# EasyedaPrj_POCKET_DICE_2026-03-14.net
KiCad netlist of a schematic drawn in EasyEDA Pro
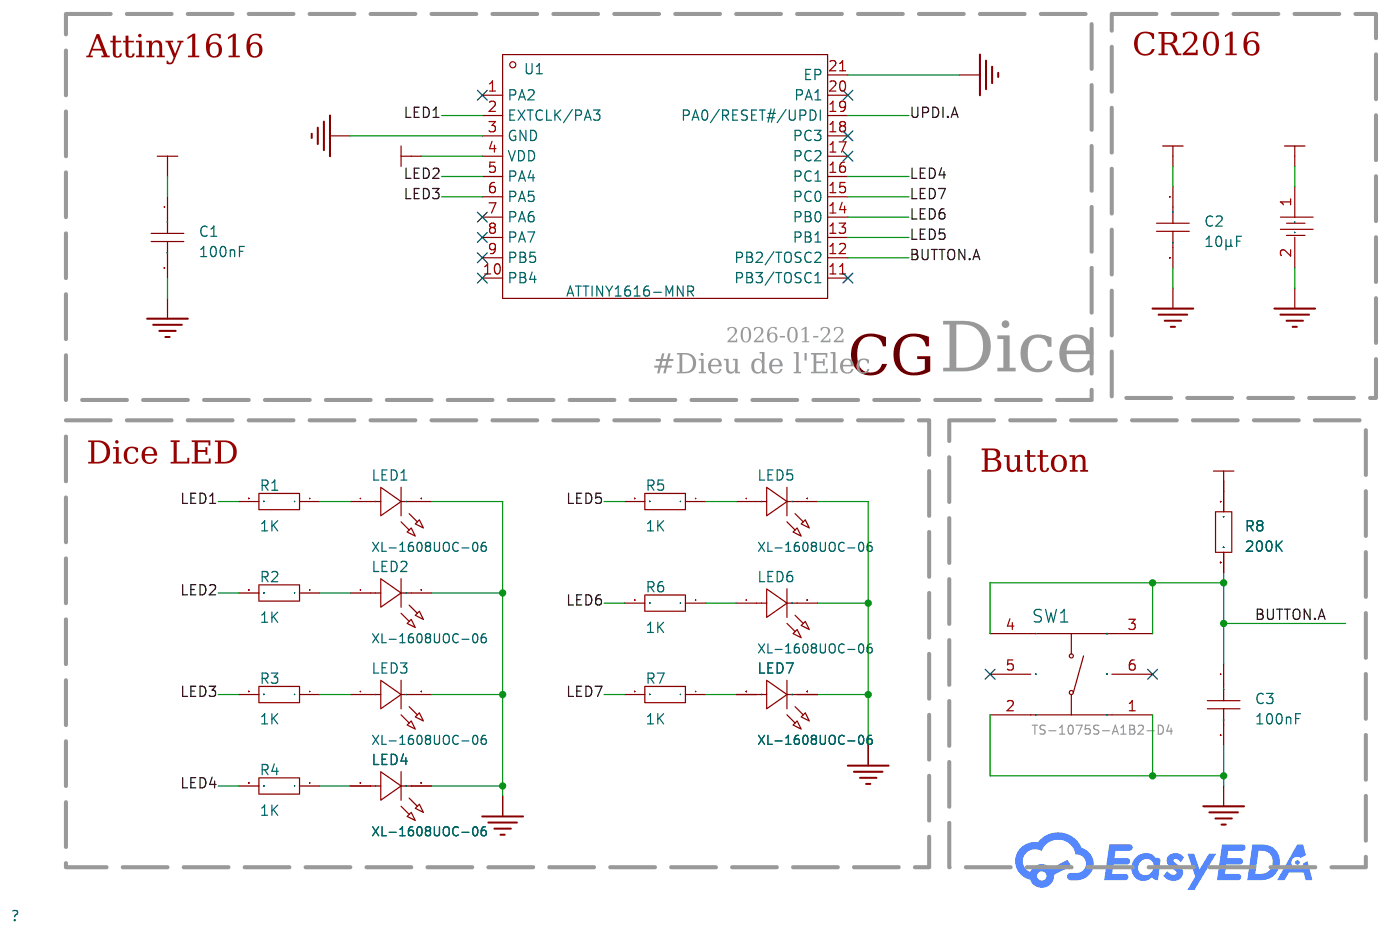
[diagram p0: schematic sheet]

(export (version "E")
  (design (tool "Eeschema 10.0.6"))
  (components
    (comp (ref "C1")
      (value "100nF")
      (footprint "easyedapro:C0805")
      (libsource (lib "easyedapro") (part "CAP"))
    )
    (comp (ref "C2")
      (value "10µF")
      (footprint "easyedapro:C0805")
      (libsource (lib "easyedapro") (part "CAP"))
    )
    (comp (ref "C3")
      (value "100nF")
      (footprint "easyedapro:C0805")
      (libsource (lib "easyedapro") (part "CAP"))
    )
    (comp (ref "LED1")
      (value "XL-1608UOC-06")
      (footprint "easyedapro:LED0603-R-RD_ORANGE")
      (fields (field (name "Manufacturer") "XINGLIGHT(成兴光)"))
      (libsource (lib "easyedapro") (part "XL-1608UOC-06"))
    )
    (comp (ref "LED2")
      (value "XL-1608UOC-06")
      (footprint "easyedapro:LED0603-R-RD_ORANGE")
      (fields (field (name "Manufacturer") "XINGLIGHT(成兴光)"))
      (libsource (lib "easyedapro") (part "XL-1608UOC-06"))
    )
    (comp (ref "LED3")
      (value "XL-1608UOC-06")
      (footprint "easyedapro:LED0603-R-RD_ORANGE")
      (fields (field (name "Manufacturer") "XINGLIGHT(成兴光)"))
      (libsource (lib "easyedapro") (part "XL-1608UOC-06"))
    )
    (comp (ref "LED4")
      (value "XL-1608UOC-06")
      (footprint "easyedapro:LED0603-R-RD_ORANGE")
      (fields (field (name "Manufacturer") "XINGLIGHT(成兴光)"))
      (libsource (lib "easyedapro") (part "XL-1608UOC-06"))
    )
    (comp (ref "LED5")
      (value "XL-1608UOC-06")
      (footprint "easyedapro:LED0603-R-RD_ORANGE")
      (fields (field (name "Manufacturer") "XINGLIGHT(成兴光)"))
      (libsource (lib "easyedapro") (part "XL-1608UOC-06"))
    )
    (comp (ref "LED6")
      (value "XL-1608UOC-06")
      (footprint "easyedapro:LED0603-R-RD_ORANGE")
      (fields (field (name "Manufacturer") "XINGLIGHT(成兴光)"))
      (libsource (lib "easyedapro") (part "XL-1608UOC-06"))
    )
    (comp (ref "LED7")
      (value "XL-1608UOC-06")
      (footprint "easyedapro:LED0603-R-RD_ORANGE")
      (fields (field (name "Manufacturer") "XINGLIGHT(成兴光)"))
      (libsource (lib "easyedapro") (part "XL-1608UOC-06"))
    )
    (comp (ref "R1") (value "1K") (footprint "easyedapro:R0402") (libsource (lib "easyedapro") (part "Res")))
    (comp (ref "R2") (value "1K") (footprint "easyedapro:R0402") (libsource (lib "easyedapro") (part "Res")))
    (comp (ref "R3") (value "1K") (footprint "easyedapro:R0402") (libsource (lib "easyedapro") (part "Res")))
    (comp (ref "R4") (value "1K") (footprint "easyedapro:R0402") (libsource (lib "easyedapro") (part "Res")))
    (comp (ref "R5") (value "1K") (footprint "easyedapro:R0402") (libsource (lib "easyedapro") (part "Res")))
    (comp (ref "R6") (value "1K") (footprint "easyedapro:R0402") (libsource (lib "easyedapro") (part "Res")))
    (comp (ref "R7") (value "1K") (footprint "easyedapro:R0402") (libsource (lib "easyedapro") (part "Res")))
    (comp (ref "R8")
      (value "200K")
      (footprint "easyedapro:R0402")
      (libsource (lib "easyedapro") (part "Res"))
    )
    (comp (ref "SW1")
      (value "TS-1075S-A1B2-D4")
      (footprint "easyedapro:SW-SMD_4P-L3.1-W3.1-P2.20-LS4.0")
      (fields (field (name "Manufacturer") "Yuandi(元迪)"))
      (libsource (lib "easyedapro") (part "TS-1075S-A1B2-D4"))
    )
    (comp (ref "U1")
      (value "ATTINY1616-MNR")
      (footprint "easyedapro:QFN-20_L3.0-W3.0-P0.40-BL-EP1.7")
      (fields (field (name "Manufacturer") "MICROCHIP(美国微芯)"))
      (libsource (lib "easyedapro") (part "ATTINY1616-MNR"))
    )
    (comp (ref "U7")
      (value "MY-2016-02")
      (footprint "easyedapro:BAT-SMD_MY-2032-08")
      (fields (field (name "Manufacturer") "MYOUNG(美阳)"))
      (libsource (lib "easyedapro") (part "MY-2016-02"))
    )
  )
  (nets
    (net (code "1") (name "/BUTTON.A") (class "Default")
      (node (ref "C3") (pin "1") (pinfunction "1_1") (pintype "input"))
      (node (ref "R8") (pin "2") (pinfunction "2_2") (pintype "input"))
      (node (ref "SW1") (pin "3") (pinfunction "3_3") (pintype "input"))
      (node (ref "SW1") (pin "4") (pinfunction "4_4") (pintype "input"))
      (node (ref "U1") (pin "12") (pinfunction "PB2/TOSC2_12") (pintype "unspecified"))
    )
    (net (code "2") (name "/LED1") (class "Default")
      (node (ref "R1") (pin "2") (pinfunction "2_2") (pintype "input"))
      (node (ref "U1") (pin "2") (pinfunction "EXTCLK/PA3_2") (pintype "unspecified"))
    )
    (net (code "3") (name "/LED2") (class "Default")
      (node (ref "R2") (pin "2") (pinfunction "2_2") (pintype "input"))
      (node (ref "U1") (pin "5") (pinfunction "PA4_5") (pintype "unspecified"))
    )
    (net (code "4") (name "/LED3") (class "Default")
      (node (ref "R3") (pin "2") (pinfunction "2_2") (pintype "input"))
      (node (ref "U1") (pin "6") (pinfunction "PA5_6") (pintype "unspecified"))
    )
    (net (code "5") (name "/LED4") (class "Default")
      (node (ref "R4") (pin "2") (pinfunction "2_2") (pintype "input"))
      (node (ref "U1") (pin "16") (pinfunction "PC1_16") (pintype "unspecified"))
    )
    (net (code "6") (name "/LED5") (class "Default")
      (node (ref "R5") (pin "2") (pinfunction "2_2") (pintype "input"))
      (node (ref "U1") (pin "13") (pinfunction "PB1_13") (pintype "unspecified"))
    )
    (net (code "7") (name "/LED6") (class "Default")
      (node (ref "R6") (pin "2") (pinfunction "2_2") (pintype "input"))
      (node (ref "U1") (pin "14") (pinfunction "PB0_14") (pintype "unspecified"))
    )
    (net (code "8") (name "/LED7") (class "Default")
      (node (ref "R7") (pin "2") (pinfunction "2_2") (pintype "input"))
      (node (ref "U1") (pin "15") (pinfunction "PC0_15") (pintype "unspecified"))
    )
    (net (code "9") (name "/UPDI.A") (class "Default")
      (node (ref "U1") (pin "19") (pinfunction "PA0/RESET#/UPDI_19") (pintype "unspecified"))
    )
    (net (code "10") (name "GND.A") (class "Default")
      (node (ref "C1") (pin "2") (pinfunction "2_2") (pintype "input"))
      (node (ref "C2") (pin "2") (pinfunction "2_2") (pintype "input"))
      (node (ref "C3") (pin "2") (pinfunction "2_2") (pintype "input"))
      (node (ref "LED1") (pin "2") (pinfunction "A_2") (pintype "unspecified"))
      (node (ref "LED2") (pin "2") (pinfunction "A_2") (pintype "unspecified"))
      (node (ref "LED3") (pin "2") (pinfunction "A_2") (pintype "unspecified"))
      (node (ref "LED4") (pin "2") (pinfunction "A_2") (pintype "unspecified"))
      (node (ref "LED5") (pin "2") (pinfunction "A_2") (pintype "unspecified"))
      (node (ref "LED6") (pin "2") (pinfunction "A_2") (pintype "unspecified"))
      (node (ref "LED7") (pin "2") (pinfunction "A_2") (pintype "unspecified"))
      (node (ref "SW1") (pin "1") (pinfunction "1_1") (pintype "input"))
      (node (ref "SW1") (pin "2") (pinfunction "2_2") (pintype "input"))
      (node (ref "U1") (pin "21") (pinfunction "EP_21") (pintype "unspecified"))
      (node (ref "U1") (pin "3") (pinfunction "GND_3") (pintype "unspecified"))
      (node (ref "U7") (pin "2") (pinfunction "2_2") (pintype "input"))
    )
    (net (code "11") (name "Net-(LED1-K)") (class "Default")
      (node (ref "LED1") (pin "1") (pinfunction "K_1") (pintype "unspecified"))
      (node (ref "R1") (pin "1") (pinfunction "1_1") (pintype "input"))
    )
    (net (code "12") (name "Net-(LED2-K)") (class "Default")
      (node (ref "LED2") (pin "1") (pinfunction "K_1") (pintype "unspecified"))
      (node (ref "R2") (pin "1") (pinfunction "1_1") (pintype "input"))
    )
    (net (code "13") (name "Net-(LED3-K)") (class "Default")
      (node (ref "LED3") (pin "1") (pinfunction "K_1") (pintype "unspecified"))
      (node (ref "R3") (pin "1") (pinfunction "1_1") (pintype "input"))
    )
    (net (code "14") (name "Net-(LED4-K)") (class "Default")
      (node (ref "LED4") (pin "1") (pinfunction "K_1") (pintype "unspecified"))
      (node (ref "R4") (pin "1") (pinfunction "1_1") (pintype "input"))
    )
    (net (code "15") (name "Net-(LED5-K)") (class "Default")
      (node (ref "LED5") (pin "1") (pinfunction "K_1") (pintype "unspecified"))
      (node (ref "R5") (pin "1") (pinfunction "1_1") (pintype "input"))
    )
    (net (code "16") (name "Net-(LED6-K)") (class "Default")
      (node (ref "LED6") (pin "1") (pinfunction "K_1") (pintype "unspecified"))
      (node (ref "R6") (pin "1") (pinfunction "1_1") (pintype "input"))
    )
    (net (code "17") (name "Net-(LED7-K)") (class "Default")
      (node (ref "LED7") (pin "1") (pinfunction "K_1") (pintype "unspecified"))
      (node (ref "R7") (pin "1") (pinfunction "1_1") (pintype "input"))
    )
    (net (code "18") (name "VDD.A") (class "Default")
      (node (ref "C1") (pin "1") (pinfunction "1_1") (pintype "input"))
      (node (ref "C2") (pin "1") (pinfunction "1_1") (pintype "input"))
      (node (ref "R8") (pin "1") (pinfunction "1_1") (pintype "input"))
      (node (ref "U1") (pin "4") (pinfunction "VDD_4") (pintype "unspecified"))
      (node (ref "U7") (pin "1") (pinfunction "1_1") (pintype "input"))
    )
    (net (code "19") (name "unconnected-(SW1-Pad5)") (class "Default")
      (node (ref "SW1") (pin "5") (pinfunction "5_5") (pintype "input+no_connect"))
    )
    (net (code "20") (name "unconnected-(SW1-Pad6)") (class "Default")
      (node (ref "SW1") (pin "6") (pinfunction "6_6") (pintype "input+no_connect"))
    )
    (net (code "21") (name "unconnected-(U1-PA1-Pad20)") (class "Default")
      (node (ref "U1") (pin "20") (pinfunction "PA1_20") (pintype "unspecified+no_connect"))
    )
    (net (code "22") (name "unconnected-(U1-PA2-Pad1)") (class "Default")
      (node (ref "U1") (pin "1") (pinfunction "PA2_1") (pintype "unspecified+no_connect"))
    )
    (net (code "23") (name "unconnected-(U1-PA6-Pad7)") (class "Default")
      (node (ref "U1") (pin "7") (pinfunction "PA6_7") (pintype "unspecified+no_connect"))
    )
    (net (code "24") (name "unconnected-(U1-PA7-Pad8)") (class "Default")
      (node (ref "U1") (pin "8") (pinfunction "PA7_8") (pintype "unspecified+no_connect"))
    )
    (net (code "25") (name "unconnected-(U1-PB3{slash}TOSC1-Pad11)") (class "Default")
      (node (ref "U1") (pin "11") (pinfunction "PB3/TOSC1_11") (pintype "unspecified+no_connect"))
    )
    (net (code "26") (name "unconnected-(U1-PB4-Pad10)") (class "Default")
      (node (ref "U1") (pin "10") (pinfunction "PB4_10") (pintype "unspecified+no_connect"))
    )
    (net (code "27") (name "unconnected-(U1-PB5-Pad9)") (class "Default")
      (node (ref "U1") (pin "9") (pinfunction "PB5_9") (pintype "unspecified+no_connect"))
    )
    (net (code "28") (name "unconnected-(U1-PC2-Pad17)") (class "Default")
      (node (ref "U1") (pin "17") (pinfunction "PC2_17") (pintype "unspecified+no_connect"))
    )
    (net (code "29") (name "unconnected-(U1-PC3-Pad18)") (class "Default")
      (node (ref "U1") (pin "18") (pinfunction "PC3_18") (pintype "unspecified+no_connect"))
    )
  )
)
